# NES.net
KiCad netlist of a schematic drawn in EAGLE
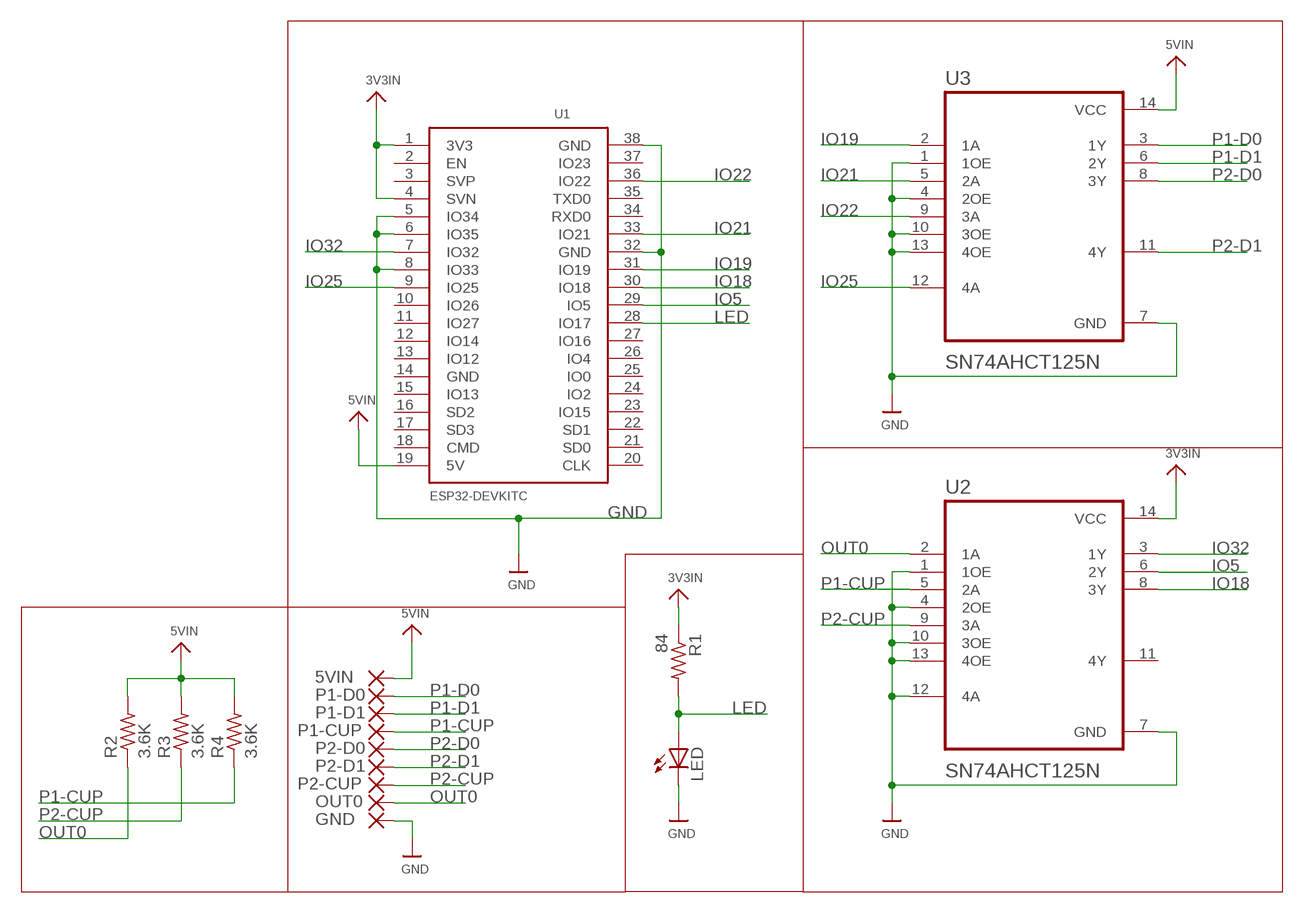
[diagram p0: schematic, sheet 1]

(export (version "E")
  (design (tool "Eeschema 10.0.6"))
  (components
    (comp (ref "5VIN")
      (value "SMD5")
      (footprint "eagle-import:SMD2,54-5,08")
      (libsource (lib "eagle-import") (part "SMD5"))
    )
    (comp (ref "GND")
      (value "SMD5")
      (footprint "eagle-import:SMD2,54-5,08")
      (libsource (lib "eagle-import") (part "SMD5"))
    )
    (comp (ref "LED")
      (value "LEDCHIPLED_1206")
      (footprint "eagle-import:CHIPLED_1206")
      (libsource (lib "eagle-import") (part "LEDCHIPLED_1206"))
    )
    (comp (ref "OUT0")
      (value "SMD5")
      (footprint "eagle-import:SMD2,54-5,08")
      (libsource (lib "eagle-import") (part "SMD5"))
    )
    (comp (ref "P1-CUP")
      (value "SMD5")
      (footprint "eagle-import:SMD2,54-5,08")
      (libsource (lib "eagle-import") (part "SMD5"))
    )
    (comp (ref "P1-D0")
      (value "SMD5")
      (footprint "eagle-import:SMD2,54-5,08")
      (libsource (lib "eagle-import") (part "SMD5"))
    )
    (comp (ref "P1-D1")
      (value "SMD5")
      (footprint "eagle-import:SMD2,54-5,08")
      (libsource (lib "eagle-import") (part "SMD5"))
    )
    (comp (ref "P2-CUP")
      (value "SMD5")
      (footprint "eagle-import:SMD2,54-5,08")
      (libsource (lib "eagle-import") (part "SMD5"))
    )
    (comp (ref "P2-D0")
      (value "SMD5")
      (footprint "eagle-import:SMD2,54-5,08")
      (libsource (lib "eagle-import") (part "SMD5"))
    )
    (comp (ref "P2-D1")
      (value "SMD5")
      (footprint "eagle-import:SMD2,54-5,08")
      (libsource (lib "eagle-import") (part "SMD5"))
    )
    (comp (ref "R1")
      (value "84")
      (footprint "eagle-import:R1206")
      (libsource (lib "eagle-import") (part "R-US_R1206"))
    )
    (comp (ref "R2")
      (value "3.6K")
      (footprint "eagle-import:R1206")
      (libsource (lib "eagle-import") (part "adafruit_420_R-US_R1206"))
    )
    (comp (ref "R3")
      (value "3.6K")
      (footprint "eagle-import:R1206")
      (libsource (lib "eagle-import") (part "adafruit_420_R-US_R1206"))
    )
    (comp (ref "R4")
      (value "3.6K")
      (footprint "eagle-import:R1206")
      (libsource (lib "eagle-import") (part "adafruit_420_R-US_R1206"))
    )
    (comp (ref "U1")
      (value "ESP32DEVKITC")
      (footprint "eagle-import:ESP32-DEVKITC")
      (libsource (lib "eagle-import") (part "ESP32DEVKITC"))
    )
    (comp (ref "U2")
      (value "SN74AHCT125N")
      (footprint "eagle-import:DIP794W45P254L1969H508Q14")
      (fields (field (name "MF") "Texas Instruments"))
      (libsource (lib "eagle-import") (part "SN74AHCT125N"))
    )
    (comp (ref "U3")
      (value "SN74AHCT125N")
      (footprint "eagle-import:DIP794W45P254L1969H508Q14")
      (fields (field (name "MF") "Texas Instruments"))
      (libsource (lib "eagle-import") (part "SN74AHCT125N"))
    )
  )
  (nets
    (net (code "1") (name "/IO5") (class "Default")
      (node (ref "U1") (pin "29") (pinfunction "IO5_29") (pintype "bidirectional"))
      (node (ref "U2") (pin "6") (pinfunction "2Y_6") (pintype "output"))
    )
    (net (code "2") (name "/IO18") (class "Default")
      (node (ref "U1") (pin "30") (pinfunction "IO18_30") (pintype "bidirectional"))
      (node (ref "U2") (pin "8") (pinfunction "3Y_8") (pintype "output"))
    )
    (net (code "3") (name "/IO19") (class "Default")
      (node (ref "U1") (pin "31") (pinfunction "IO19_31") (pintype "bidirectional"))
      (node (ref "U3") (pin "2") (pinfunction "1A_2") (pintype "input"))
    )
    (net (code "4") (name "/IO21") (class "Default")
      (node (ref "U1") (pin "33") (pinfunction "IO21_33") (pintype "bidirectional"))
      (node (ref "U3") (pin "5") (pinfunction "2A_5") (pintype "input"))
    )
    (net (code "5") (name "/IO22") (class "Default")
      (node (ref "U1") (pin "36") (pinfunction "IO22_36") (pintype "bidirectional"))
      (node (ref "U3") (pin "9") (pinfunction "3A_9") (pintype "input"))
    )
    (net (code "6") (name "/IO25") (class "Default")
      (node (ref "U1") (pin "9") (pinfunction "IO25_9") (pintype "bidirectional"))
      (node (ref "U3") (pin "12") (pinfunction "4A_12") (pintype "bidirectional"))
    )
    (net (code "7") (name "/IO32") (class "Default")
      (node (ref "U1") (pin "7") (pinfunction "IO32_7") (pintype "bidirectional"))
      (node (ref "U2") (pin "3") (pinfunction "1Y_3") (pintype "output"))
    )
    (net (code "8") (name "/LED") (class "Default")
      (node (ref "LED") (pin "A") (pinfunction "A_A") (pintype "passive"))
      (node (ref "R1") (pin "2") (pinfunction "2_2") (pintype "passive"))
      (node (ref "U1") (pin "28") (pinfunction "IO17_28") (pintype "bidirectional"))
    )
    (net (code "9") (name "/OUT0") (class "Default")
      (node (ref "OUT0") (pin "1") (pinfunction "P_1") (pintype "passive"))
      (node (ref "R2") (pin "1") (pinfunction "1_1") (pintype "passive"))
      (node (ref "U2") (pin "2") (pinfunction "1A_2") (pintype "input"))
    )
    (net (code "10") (name "/P1-CUP") (class "Default")
      (node (ref "P1-CUP") (pin "1") (pinfunction "P_1") (pintype "passive"))
      (node (ref "R4") (pin "1") (pinfunction "1_1") (pintype "passive"))
      (node (ref "U2") (pin "5") (pinfunction "2A_5") (pintype "input"))
    )
    (net (code "11") (name "/P1-D0") (class "Default")
      (node (ref "P1-D0") (pin "1") (pinfunction "P_1") (pintype "passive"))
      (node (ref "U3") (pin "3") (pinfunction "1Y_3") (pintype "output"))
    )
    (net (code "12") (name "/P1-D1") (class "Default")
      (node (ref "P1-D1") (pin "1") (pinfunction "P_1") (pintype "passive"))
      (node (ref "U3") (pin "6") (pinfunction "2Y_6") (pintype "output"))
    )
    (net (code "13") (name "/P2-CUP") (class "Default")
      (node (ref "P2-CUP") (pin "1") (pinfunction "P_1") (pintype "passive"))
      (node (ref "R3") (pin "1") (pinfunction "1_1") (pintype "passive"))
      (node (ref "U2") (pin "9") (pinfunction "3A_9") (pintype "input"))
    )
    (net (code "14") (name "/P2-D0") (class "Default")
      (node (ref "P2-D0") (pin "1") (pinfunction "P_1") (pintype "passive"))
      (node (ref "U3") (pin "8") (pinfunction "3Y_8") (pintype "output"))
    )
    (net (code "15") (name "/P2-D1") (class "Default")
      (node (ref "P2-D1") (pin "1") (pinfunction "P_1") (pintype "passive"))
      (node (ref "U3") (pin "11") (pinfunction "4Y_11") (pintype "output"))
    )
    (net (code "16") (name "3V3IN") (class "Default")
      (node (ref "R1") (pin "1") (pinfunction "1_1") (pintype "passive"))
      (node (ref "U1") (pin "1") (pinfunction "3V3_1") (pintype "bidirectional"))
      (node (ref "U1") (pin "4") (pinfunction "SVN_4") (pintype "bidirectional"))
      (node (ref "U2") (pin "14") (pinfunction "VCC_14") (pintype "power_in"))
    )
    (net (code "17") (name "5VIN") (class "Default")
      (node (ref "5VIN") (pin "1") (pinfunction "P_1") (pintype "passive"))
      (node (ref "R2") (pin "2") (pinfunction "2_2") (pintype "passive"))
      (node (ref "R3") (pin "2") (pinfunction "2_2") (pintype "passive"))
      (node (ref "R4") (pin "2") (pinfunction "2_2") (pintype "passive"))
      (node (ref "U1") (pin "19") (pinfunction "5V_19") (pintype "bidirectional"))
      (node (ref "U3") (pin "14") (pinfunction "VCC_14") (pintype "power_in"))
    )
    (net (code "18") (name "GND") (class "Default")
      (node (ref "GND") (pin "1") (pinfunction "P_1") (pintype "passive"))
      (node (ref "LED") (pin "C") (pinfunction "C_C") (pintype "passive"))
      (node (ref "U1") (pin "32") (pinfunction "GND_32") (pintype "bidirectional"))
      (node (ref "U1") (pin "38") (pinfunction "GND_38") (pintype "bidirectional"))
      (node (ref "U1") (pin "5") (pinfunction "IO34_5") (pintype "bidirectional"))
      (node (ref "U1") (pin "6") (pinfunction "IO35_6") (pintype "bidirectional"))
      (node (ref "U1") (pin "8") (pinfunction "IO33_8") (pintype "bidirectional"))
      (node (ref "U2") (pin "1") (pinfunction "1OE_1") (pintype "input"))
      (node (ref "U2") (pin "10") (pinfunction "3OE_10") (pintype "input"))
      (node (ref "U2") (pin "12") (pinfunction "4A_12") (pintype "bidirectional"))
      (node (ref "U2") (pin "13") (pinfunction "4OE_13") (pintype "input"))
      (node (ref "U2") (pin "4") (pinfunction "2OE_4") (pintype "input"))
      (node (ref "U2") (pin "7") (pinfunction "GND_7") (pintype "power_in"))
      (node (ref "U3") (pin "1") (pinfunction "1OE_1") (pintype "input"))
      (node (ref "U3") (pin "10") (pinfunction "3OE_10") (pintype "input"))
      (node (ref "U3") (pin "13") (pinfunction "4OE_13") (pintype "input"))
      (node (ref "U3") (pin "4") (pinfunction "2OE_4") (pintype "input"))
      (node (ref "U3") (pin "7") (pinfunction "GND_7") (pintype "power_in"))
    )
    (net (code "19") (name "unconnected-(U1-CLK-Pad20)") (class "Default")
      (node (ref "U1") (pin "20") (pinfunction "CLK_20") (pintype "bidirectional"))
    )
    (net (code "20") (name "unconnected-(U1-CMD-Pad18)") (class "Default")
      (node (ref "U1") (pin "18") (pinfunction "CMD_18") (pintype "bidirectional"))
    )
    (net (code "21") (name "unconnected-(U1-EN-Pad2)") (class "Default")
      (node (ref "U1") (pin "2") (pinfunction "EN_2") (pintype "bidirectional"))
    )
    (net (code "22") (name "unconnected-(U1-GND-Pad14)") (class "Default")
      (node (ref "U1") (pin "14") (pinfunction "GND_14") (pintype "bidirectional"))
    )
    (net (code "23") (name "unconnected-(U1-IO0-Pad25)") (class "Default")
      (node (ref "U1") (pin "25") (pinfunction "IO0_25") (pintype "bidirectional"))
    )
    (net (code "24") (name "unconnected-(U1-IO2-Pad24)") (class "Default")
      (node (ref "U1") (pin "24") (pinfunction "IO2_24") (pintype "bidirectional"))
    )
    (net (code "25") (name "unconnected-(U1-IO4-Pad26)") (class "Default")
      (node (ref "U1") (pin "26") (pinfunction "IO4_26") (pintype "bidirectional"))
    )
    (net (code "26") (name "unconnected-(U1-IO12-Pad13)") (class "Default")
      (node (ref "U1") (pin "13") (pinfunction "IO12_13") (pintype "bidirectional"))
    )
    (net (code "27") (name "unconnected-(U1-IO13-Pad15)") (class "Default")
      (node (ref "U1") (pin "15") (pinfunction "IO13_15") (pintype "bidirectional"))
    )
    (net (code "28") (name "unconnected-(U1-IO14-Pad12)") (class "Default")
      (node (ref "U1") (pin "12") (pinfunction "IO14_12") (pintype "bidirectional"))
    )
    (net (code "29") (name "unconnected-(U1-IO15-Pad23)") (class "Default")
      (node (ref "U1") (pin "23") (pinfunction "IO15_23") (pintype "bidirectional"))
    )
    (net (code "30") (name "unconnected-(U1-IO16-Pad27)") (class "Default")
      (node (ref "U1") (pin "27") (pinfunction "IO16_27") (pintype "bidirectional"))
    )
    (net (code "31") (name "unconnected-(U1-IO23-Pad37)") (class "Default")
      (node (ref "U1") (pin "37") (pinfunction "IO23_37") (pintype "bidirectional"))
    )
    (net (code "32") (name "unconnected-(U1-IO26-Pad10)") (class "Default")
      (node (ref "U1") (pin "10") (pinfunction "IO26_10") (pintype "bidirectional"))
    )
    (net (code "33") (name "unconnected-(U1-IO27-Pad11)") (class "Default")
      (node (ref "U1") (pin "11") (pinfunction "IO27_11") (pintype "bidirectional"))
    )
    (net (code "34") (name "unconnected-(U1-RXD0-Pad34)") (class "Default")
      (node (ref "U1") (pin "34") (pinfunction "RXD0_34") (pintype "bidirectional"))
    )
    (net (code "35") (name "unconnected-(U1-SD0-Pad21)") (class "Default")
      (node (ref "U1") (pin "21") (pinfunction "SD0_21") (pintype "bidirectional"))
    )
    (net (code "36") (name "unconnected-(U1-SD1-Pad22)") (class "Default")
      (node (ref "U1") (pin "22") (pinfunction "SD1_22") (pintype "bidirectional"))
    )
    (net (code "37") (name "unconnected-(U1-SD2-Pad16)") (class "Default")
      (node (ref "U1") (pin "16") (pinfunction "SD2_16") (pintype "bidirectional"))
    )
    (net (code "38") (name "unconnected-(U1-SD3-Pad17)") (class "Default")
      (node (ref "U1") (pin "17") (pinfunction "SD3_17") (pintype "bidirectional"))
    )
    (net (code "39") (name "unconnected-(U1-SVP-Pad3)") (class "Default")
      (node (ref "U1") (pin "3") (pinfunction "SVP_3") (pintype "bidirectional"))
    )
    (net (code "40") (name "unconnected-(U1-TXD0-Pad35)") (class "Default")
      (node (ref "U1") (pin "35") (pinfunction "TXD0_35") (pintype "bidirectional"))
    )
    (net (code "41") (name "unconnected-(U2-4Y-Pad11)") (class "Default")
      (node (ref "U2") (pin "11") (pinfunction "4Y_11") (pintype "output"))
    )
  )
)
